# AVES_Telemetria_Eagle.net
KiCad netlist of a schematic drawn in EAGLE
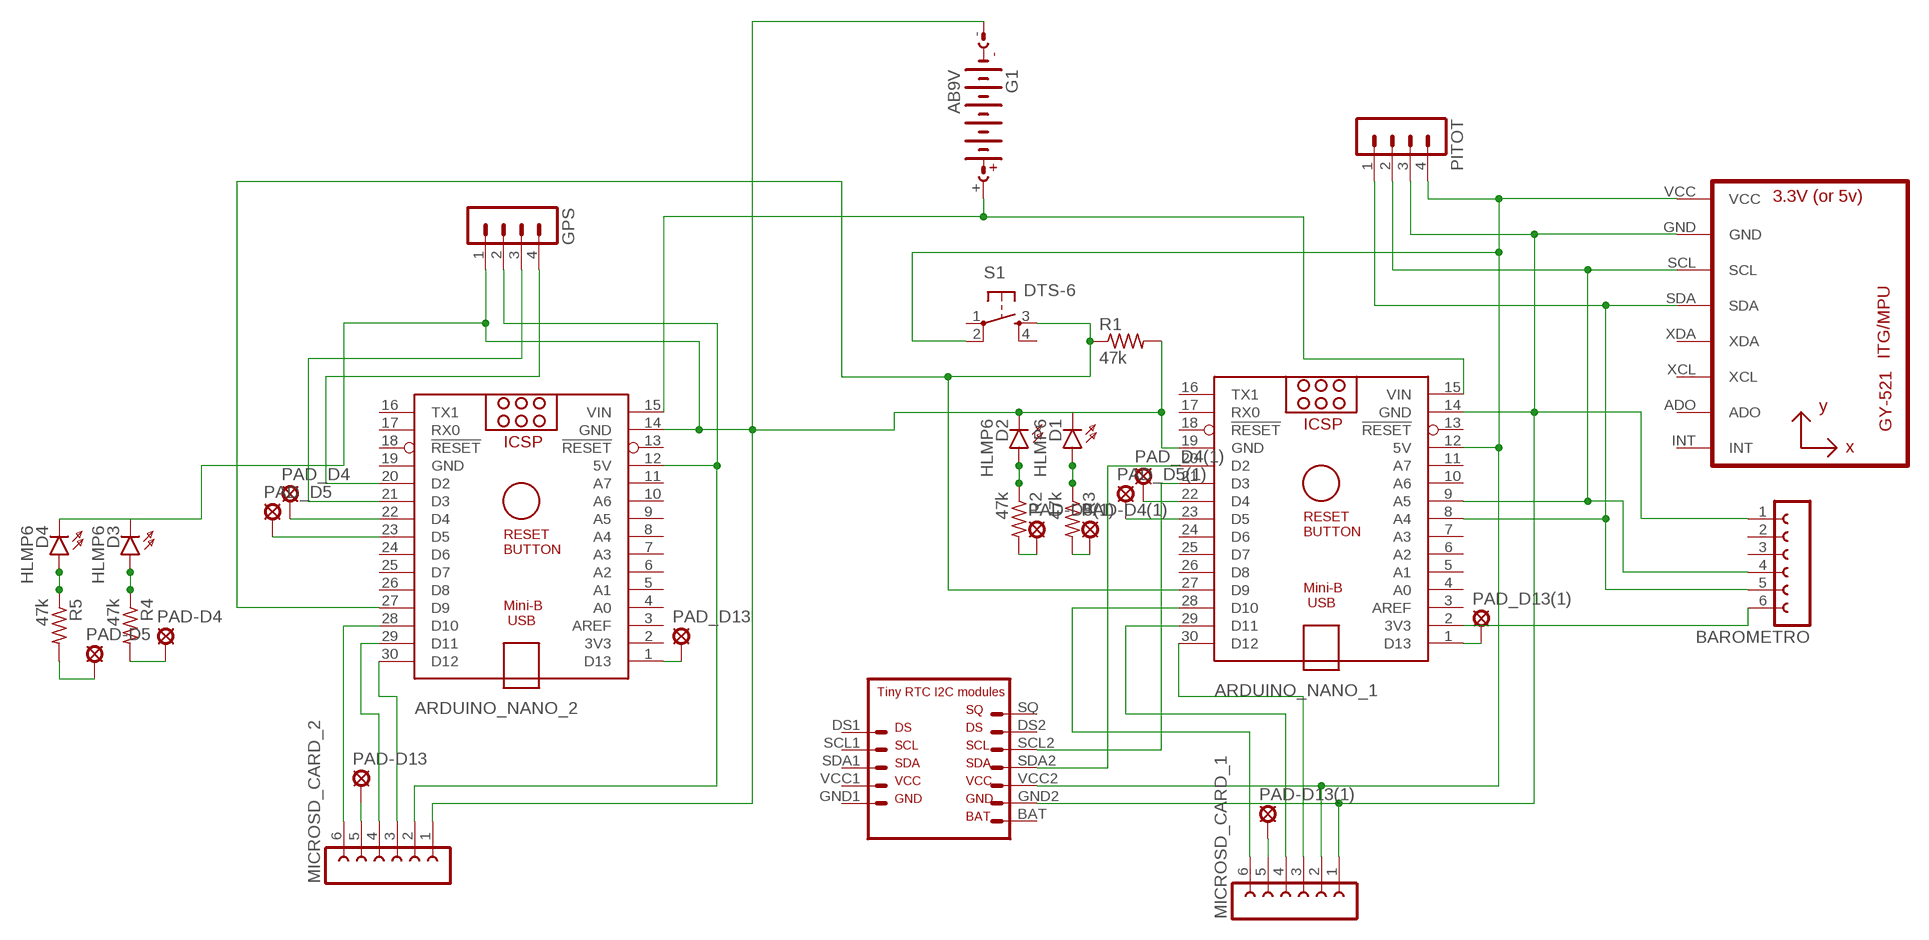
[diagram p0: schematic, sheet 1]

(export (version "E")
  (design (tool "Eeschema 10.0.6"))
  (components
    (comp (ref "ARDUINO_NANO_1")
      (value "ARDUINO_NANO")
      (footprint "eagle-import:ARDUINO_NANO")
      (libsource (lib "eagle-import") (part "ARDUINO_NANO"))
    )
    (comp (ref "ARDUINO_NANO_2")
      (value "ARDUINO_NANO")
      (footprint "eagle-import:ARDUINO_NANO")
      (libsource (lib "eagle-import") (part "ARDUINO_NANO"))
    )
    (comp (ref "BAROMETRO")
      (value "FE06-1")
      (footprint "eagle-import:FE06")
      (libsource (lib "eagle-import") (part "FE06-1"))
    )
    (comp (ref "D1")
      (value "HLMP6")
      (footprint "eagle-import:HLMP6")
      (fields (field (name "MF") "AGILENT TECHNOLOGIES") (field (name "MPN") "HLMP-6500"))
      (libsource (lib "eagle-import") (part "HLMP6"))
    )
    (comp (ref "D2")
      (value "HLMP6")
      (footprint "eagle-import:HLMP6")
      (fields (field (name "MF") "AGILENT TECHNOLOGIES") (field (name "MPN") "HLMP-6500"))
      (libsource (lib "eagle-import") (part "HLMP6"))
    )
    (comp (ref "D3")
      (value "HLMP6")
      (footprint "eagle-import:HLMP6")
      (fields (field (name "MF") "AGILENT TECHNOLOGIES") (field (name "MPN") "HLMP-6500"))
      (libsource (lib "eagle-import") (part "HLMP6"))
    )
    (comp (ref "D4")
      (value "HLMP6")
      (footprint "eagle-import:HLMP6")
      (fields (field (name "MF") "AGILENT TECHNOLOGIES") (field (name "MPN") "HLMP-6500"))
      (libsource (lib "eagle-import") (part "HLMP6"))
    )
    (comp (ref "G1")
      (value "AB9V")
      (footprint "eagle-import:AB9V")
      (libsource (lib "eagle-import") (part "AB9V"))
    )
    (comp (ref "GPS")
      (value "MA04-1")
      (footprint "eagle-import:MA04-1")
      (libsource (lib "eagle-import") (part "MA04-1"))
    )
    (comp (ref "MICROSD_CARD_1")
      (value "FE06-1")
      (footprint "eagle-import:FE06")
      (libsource (lib "eagle-import") (part "FE06-1"))
    )
    (comp (ref "MICROSD_CARD_2")
      (value "FE06-1")
      (footprint "eagle-import:FE06")
      (libsource (lib "eagle-import") (part "FE06-1"))
    )
    (comp (ref "PAD-D4")
      (value "LSP10")
      (footprint "eagle-import:LSP10")
      (libsource (lib "eagle-import") (part "LSP10"))
    )
    (comp (ref "PAD-D4(1)")
      (value "LSP10")
      (footprint "eagle-import:LSP10")
      (libsource (lib "eagle-import") (part "LSP10"))
    )
    (comp (ref "PAD-D5")
      (value "LSP10")
      (footprint "eagle-import:LSP10")
      (libsource (lib "eagle-import") (part "LSP10"))
    )
    (comp (ref "PAD-D5(1)")
      (value "LSP10")
      (footprint "eagle-import:LSP10")
      (libsource (lib "eagle-import") (part "LSP10"))
    )
    (comp (ref "PAD-D13")
      (value "LSP10")
      (footprint "eagle-import:LSP10")
      (libsource (lib "eagle-import") (part "LSP10"))
    )
    (comp (ref "PAD-D13(1)")
      (value "LSP10")
      (footprint "eagle-import:LSP10")
      (libsource (lib "eagle-import") (part "LSP10"))
    )
    (comp (ref "PAD_D4")
      (value "LSP10")
      (footprint "eagle-import:LSP10")
      (libsource (lib "eagle-import") (part "LSP10"))
    )
    (comp (ref "PAD_D4(1)")
      (value "LSP10")
      (footprint "eagle-import:LSP10")
      (libsource (lib "eagle-import") (part "LSP10"))
    )
    (comp (ref "PAD_D5")
      (value "LSP10")
      (footprint "eagle-import:LSP10")
      (libsource (lib "eagle-import") (part "LSP10"))
    )
    (comp (ref "PAD_D5(1)")
      (value "LSP10")
      (footprint "eagle-import:LSP10")
      (libsource (lib "eagle-import") (part "LSP10"))
    )
    (comp (ref "PAD_D13")
      (value "LSP10")
      (footprint "eagle-import:LSP10")
      (libsource (lib "eagle-import") (part "LSP10"))
    )
    (comp (ref "PAD_D13(1)")
      (value "LSP10")
      (footprint "eagle-import:LSP10")
      (libsource (lib "eagle-import") (part "LSP10"))
    )
    (comp (ref "PITOT")
      (value "MA04-1")
      (footprint "eagle-import:MA04-1")
      (libsource (lib "eagle-import") (part "MA04-1"))
    )
    (comp (ref "R1")
      (value "47k")
      (footprint "eagle-import:0204_5")
      (libsource (lib "eagle-import") (part "R-US_0204/5"))
    )
    (comp (ref "R2")
      (value "47k")
      (footprint "eagle-import:0204_5")
      (libsource (lib "eagle-import") (part "R-US_0204/5"))
    )
    (comp (ref "R3")
      (value "47k")
      (footprint "eagle-import:0204_5")
      (libsource (lib "eagle-import") (part "R-US_0204/5"))
    )
    (comp (ref "R4")
      (value "47k")
      (footprint "eagle-import:0204_5")
      (libsource (lib "eagle-import") (part "R-US_0204/5"))
    )
    (comp (ref "R5")
      (value "47k")
      (footprint "eagle-import:0204_5")
      (libsource (lib "eagle-import") (part "R-US_0204/5"))
    )
    (comp (ref "S1")
      (value "DTS-6")
      (footprint "eagle-import:DTS-6")
      (libsource (lib "eagle-import") (part "DTS-6"))
    )
    (comp (ref "U$1")
      (value "RTC")
      (footprint "eagle-import:RTC")
      (libsource (lib "eagle-import") (part "RTC"))
    )
    (comp (ref "U1")
      (value "GY-521MPU6050")
      (footprint "eagle-import:GY-521")
      (libsource (lib "eagle-import") (part "GY-521MPU6050"))
    )
  )
  (nets
    (net (code "1") (name "/GND") (class "Default")
      (node (ref "ARDUINO_NANO_2") (pin "19") (pinfunction "GND_19") (pintype "power_in"))
    )
    (net (code "2") (name "Net-(ARDUINO_NANO_1-3V3)") (class "Default")
      (node (ref "ARDUINO_NANO_1") (pin "2") (pinfunction "3V3_2") (pintype "output"))
      (node (ref "BAROMETRO") (pin "6") (pinfunction "6_6") (pintype "passive"))
    )
    (net (code "3") (name "Net-(ARDUINO_NANO_1-5V)") (class "Default")
      (node (ref "ARDUINO_NANO_1") (pin "12") (pinfunction "5V_12") (pintype "power_in"))
      (node (ref "MICROSD_CARD_1") (pin "2") (pinfunction "2_2") (pintype "passive"))
      (node (ref "PITOT") (pin "4") (pinfunction "4_4") (pintype "passive"))
      (node (ref "S1") (pin "2") (pinfunction "2_2") (pintype "passive"))
      (node (ref "U$1") (pin "VCC2") (pinfunction "VCC2_VCC2") (pintype "passive"))
      (node (ref "U1") (pin "VCC") (pinfunction "VCC_VCC") (pintype "bidirectional"))
    )
    (net (code "4") (name "Net-(ARDUINO_NANO_1-A4)") (class "Default")
      (node (ref "ARDUINO_NANO_1") (pin "8") (pinfunction "A4_8") (pintype "bidirectional"))
      (node (ref "BAROMETRO") (pin "5") (pinfunction "5_5") (pintype "passive"))
      (node (ref "PITOT") (pin "1") (pinfunction "1_1") (pintype "passive"))
      (node (ref "U1") (pin "SDA") (pinfunction "SDA_SDA") (pintype "bidirectional"))
    )
    (net (code "5") (name "Net-(ARDUINO_NANO_1-A5)") (class "Default")
      (node (ref "ARDUINO_NANO_1") (pin "9") (pinfunction "A5_9") (pintype "bidirectional"))
      (node (ref "BAROMETRO") (pin "4") (pinfunction "4_4") (pintype "passive"))
      (node (ref "PITOT") (pin "2") (pinfunction "2_2") (pintype "passive"))
      (node (ref "U1") (pin "SCL") (pinfunction "SCL_SCL") (pintype "bidirectional"))
    )
    (net (code "6") (name "Net-(ARDUINO_NANO_1-D2)") (class "Default")
      (node (ref "ARDUINO_NANO_1") (pin "20") (pinfunction "D2_20") (pintype "bidirectional"))
      (node (ref "U$1") (pin "SDA2") (pinfunction "SDA2_SDA2") (pintype "passive"))
    )
    (net (code "7") (name "Net-(ARDUINO_NANO_1-D3)") (class "Default")
      (node (ref "ARDUINO_NANO_1") (pin "21") (pinfunction "D3_21") (pintype "bidirectional"))
      (node (ref "U$1") (pin "SCL2") (pinfunction "SCL2_SCL2") (pintype "passive"))
    )
    (net (code "8") (name "Net-(ARDUINO_NANO_1-D4)") (class "Default")
      (node (ref "ARDUINO_NANO_1") (pin "22") (pinfunction "D4_22") (pintype "bidirectional"))
      (node (ref "PAD_D4(1)") (pin "MP") (pinfunction "MP_MP") (pintype "passive"))
    )
    (net (code "9") (name "Net-(ARDUINO_NANO_1-D5)") (class "Default")
      (node (ref "ARDUINO_NANO_1") (pin "23") (pinfunction "D5_23") (pintype "bidirectional"))
      (node (ref "PAD_D5(1)") (pin "MP") (pinfunction "MP_MP") (pintype "passive"))
    )
    (net (code "10") (name "Net-(ARDUINO_NANO_1-D9)") (class "Default")
      (node (ref "ARDUINO_NANO_1") (pin "27") (pinfunction "D9_27") (pintype "bidirectional"))
      (node (ref "ARDUINO_NANO_2") (pin "27") (pinfunction "D9_27") (pintype "bidirectional"))
      (node (ref "R1") (pin "1") (pinfunction "1_1") (pintype "passive"))
      (node (ref "S1") (pin "3") (pinfunction "3_3") (pintype "passive"))
    )
    (net (code "11") (name "Net-(ARDUINO_NANO_1-D10)") (class "Default")
      (node (ref "ARDUINO_NANO_1") (pin "28") (pinfunction "D10_28") (pintype "bidirectional"))
      (node (ref "MICROSD_CARD_1") (pin "6") (pinfunction "6_6") (pintype "passive"))
    )
    (net (code "12") (name "Net-(ARDUINO_NANO_1-D11)") (class "Default")
      (node (ref "ARDUINO_NANO_1") (pin "29") (pinfunction "D11_29") (pintype "bidirectional"))
      (node (ref "MICROSD_CARD_1") (pin "4") (pinfunction "4_4") (pintype "passive"))
    )
    (net (code "13") (name "Net-(ARDUINO_NANO_1-D12)") (class "Default")
      (node (ref "ARDUINO_NANO_1") (pin "30") (pinfunction "D12_30") (pintype "bidirectional"))
      (node (ref "MICROSD_CARD_1") (pin "3") (pinfunction "3_3") (pintype "passive"))
    )
    (net (code "14") (name "Net-(ARDUINO_NANO_1-D13)") (class "Default")
      (node (ref "ARDUINO_NANO_1") (pin "1") (pinfunction "D13_1") (pintype "bidirectional"))
      (node (ref "PAD_D13(1)") (pin "MP") (pinfunction "MP_MP") (pintype "passive"))
    )
    (net (code "15") (name "Net-(ARDUINO_NANO_1-GND-Pad14)") (class "Default")
      (node (ref "ARDUINO_NANO_1") (pin "14") (pinfunction "GND_14") (pintype "power_in"))
      (node (ref "BAROMETRO") (pin "1") (pinfunction "1_1") (pintype "passive"))
      (node (ref "MICROSD_CARD_1") (pin "1") (pinfunction "1_1") (pintype "passive"))
      (node (ref "PITOT") (pin "3") (pinfunction "3_3") (pintype "passive"))
      (node (ref "U$1") (pin "GND2") (pinfunction "GND2_GND2") (pintype "passive"))
      (node (ref "U1") (pin "GND") (pinfunction "GND_GND") (pintype "bidirectional"))
    )
    (net (code "16") (name "Net-(ARDUINO_NANO_1-GND-Pad19)") (class "Default")
      (node (ref "ARDUINO_NANO_1") (pin "19") (pinfunction "GND_19") (pintype "power_in"))
      (node (ref "ARDUINO_NANO_2") (pin "14") (pinfunction "GND_14") (pintype "power_in"))
      (node (ref "D1") (pin "K") (pinfunction "K_K") (pintype "passive"))
      (node (ref "D2") (pin "K") (pinfunction "K_K") (pintype "passive"))
      (node (ref "D3") (pin "K") (pinfunction "K_K") (pintype "passive"))
      (node (ref "D4") (pin "K") (pinfunction "K_K") (pintype "passive"))
      (node (ref "G1") (pin "-") (pinfunction "-_-") (pintype "passive"))
      (node (ref "GPS") (pin "1") (pinfunction "1_1") (pintype "passive"))
      (node (ref "MICROSD_CARD_2") (pin "1") (pinfunction "1_1") (pintype "passive"))
      (node (ref "R1") (pin "2") (pinfunction "2_2") (pintype "passive"))
    )
    (net (code "17") (name "Net-(ARDUINO_NANO_1-VIN)") (class "Default")
      (node (ref "ARDUINO_NANO_1") (pin "15") (pinfunction "VIN_15") (pintype "power_in"))
      (node (ref "ARDUINO_NANO_2") (pin "15") (pinfunction "VIN_15") (pintype "power_in"))
      (node (ref "G1") (pin "+") (pinfunction "+_+") (pintype "passive"))
    )
    (net (code "18") (name "Net-(ARDUINO_NANO_2-5V)") (class "Default")
      (node (ref "ARDUINO_NANO_2") (pin "12") (pinfunction "5V_12") (pintype "power_in"))
      (node (ref "GPS") (pin "2") (pinfunction "2_2") (pintype "passive"))
      (node (ref "MICROSD_CARD_2") (pin "2") (pinfunction "2_2") (pintype "passive"))
    )
    (net (code "19") (name "Net-(ARDUINO_NANO_2-D2)") (class "Default")
      (node (ref "ARDUINO_NANO_2") (pin "20") (pinfunction "D2_20") (pintype "bidirectional"))
      (node (ref "GPS") (pin "4") (pinfunction "4_4") (pintype "passive"))
    )
    (net (code "20") (name "Net-(ARDUINO_NANO_2-D3)") (class "Default")
      (node (ref "ARDUINO_NANO_2") (pin "21") (pinfunction "D3_21") (pintype "bidirectional"))
      (node (ref "GPS") (pin "3") (pinfunction "3_3") (pintype "passive"))
    )
    (net (code "21") (name "Net-(ARDUINO_NANO_2-D4)") (class "Default")
      (node (ref "ARDUINO_NANO_2") (pin "22") (pinfunction "D4_22") (pintype "bidirectional"))
      (node (ref "PAD_D4") (pin "MP") (pinfunction "MP_MP") (pintype "passive"))
    )
    (net (code "22") (name "Net-(ARDUINO_NANO_2-D5)") (class "Default")
      (node (ref "ARDUINO_NANO_2") (pin "23") (pinfunction "D5_23") (pintype "bidirectional"))
      (node (ref "PAD_D5") (pin "MP") (pinfunction "MP_MP") (pintype "passive"))
    )
    (net (code "23") (name "Net-(ARDUINO_NANO_2-D10)") (class "Default")
      (node (ref "ARDUINO_NANO_2") (pin "28") (pinfunction "D10_28") (pintype "bidirectional"))
      (node (ref "MICROSD_CARD_2") (pin "6") (pinfunction "6_6") (pintype "passive"))
    )
    (net (code "24") (name "Net-(ARDUINO_NANO_2-D11)") (class "Default")
      (node (ref "ARDUINO_NANO_2") (pin "29") (pinfunction "D11_29") (pintype "bidirectional"))
      (node (ref "MICROSD_CARD_2") (pin "4") (pinfunction "4_4") (pintype "passive"))
    )
    (net (code "25") (name "Net-(ARDUINO_NANO_2-D12)") (class "Default")
      (node (ref "ARDUINO_NANO_2") (pin "30") (pinfunction "D12_30") (pintype "bidirectional"))
      (node (ref "MICROSD_CARD_2") (pin "3") (pinfunction "3_3") (pintype "passive"))
    )
    (net (code "26") (name "Net-(ARDUINO_NANO_2-D13)") (class "Default")
      (node (ref "ARDUINO_NANO_2") (pin "1") (pinfunction "D13_1") (pintype "bidirectional"))
      (node (ref "PAD_D13") (pin "MP") (pinfunction "MP_MP") (pintype "passive"))
    )
    (net (code "27") (name "Net-(D1-PadA)") (class "Default")
      (node (ref "D1") (pin "A") (pinfunction "A_A") (pintype "passive"))
      (node (ref "R3") (pin "1") (pinfunction "1_1") (pintype "passive"))
    )
    (net (code "28") (name "Net-(D2-PadA)") (class "Default")
      (node (ref "D2") (pin "A") (pinfunction "A_A") (pintype "passive"))
      (node (ref "R2") (pin "1") (pinfunction "1_1") (pintype "passive"))
    )
    (net (code "29") (name "Net-(D3-PadA)") (class "Default")
      (node (ref "D3") (pin "A") (pinfunction "A_A") (pintype "passive"))
      (node (ref "R4") (pin "1") (pinfunction "1_1") (pintype "passive"))
    )
    (net (code "30") (name "Net-(D4-PadA)") (class "Default")
      (node (ref "D4") (pin "A") (pinfunction "A_A") (pintype "passive"))
      (node (ref "R5") (pin "1") (pinfunction "1_1") (pintype "passive"))
    )
    (net (code "31") (name "Net-(MICROSD_CARD_1-Pad5)") (class "Default")
      (node (ref "MICROSD_CARD_1") (pin "5") (pinfunction "5_5") (pintype "passive"))
      (node (ref "PAD-D13(1)") (pin "MP") (pinfunction "MP_MP") (pintype "passive"))
    )
    (net (code "32") (name "Net-(MICROSD_CARD_2-Pad5)") (class "Default")
      (node (ref "MICROSD_CARD_2") (pin "5") (pinfunction "5_5") (pintype "passive"))
      (node (ref "PAD-D13") (pin "MP") (pinfunction "MP_MP") (pintype "passive"))
    )
    (net (code "33") (name "Net-(PAD-D4(1)-PadMP)") (class "Default")
      (node (ref "PAD-D4(1)") (pin "MP") (pinfunction "MP_MP") (pintype "passive"))
      (node (ref "R3") (pin "2") (pinfunction "2_2") (pintype "passive"))
    )
    (net (code "34") (name "Net-(PAD-D4-PadMP)") (class "Default")
      (node (ref "PAD-D4") (pin "MP") (pinfunction "MP_MP") (pintype "passive"))
      (node (ref "R4") (pin "2") (pinfunction "2_2") (pintype "passive"))
    )
    (net (code "35") (name "Net-(PAD-D5(1)-PadMP)") (class "Default")
      (node (ref "PAD-D5(1)") (pin "MP") (pinfunction "MP_MP") (pintype "passive"))
      (node (ref "R2") (pin "2") (pinfunction "2_2") (pintype "passive"))
    )
    (net (code "36") (name "Net-(PAD-D5-PadMP)") (class "Default")
      (node (ref "PAD-D5") (pin "MP") (pinfunction "MP_MP") (pintype "passive"))
      (node (ref "R5") (pin "2") (pinfunction "2_2") (pintype "passive"))
    )
    (net (code "37") (name "unconnected-(ARDUINO_NANO_1-A0-Pad4)") (class "Default")
      (node (ref "ARDUINO_NANO_1") (pin "4") (pinfunction "A0_4") (pintype "bidirectional"))
    )
    (net (code "38") (name "unconnected-(ARDUINO_NANO_1-A1-Pad5)") (class "Default")
      (node (ref "ARDUINO_NANO_1") (pin "5") (pinfunction "A1_5") (pintype "bidirectional"))
    )
    (net (code "39") (name "unconnected-(ARDUINO_NANO_1-A2-Pad6)") (class "Default")
      (node (ref "ARDUINO_NANO_1") (pin "6") (pinfunction "A2_6") (pintype "bidirectional"))
    )
    (net (code "40") (name "unconnected-(ARDUINO_NANO_1-A3-Pad7)") (class "Default")
      (node (ref "ARDUINO_NANO_1") (pin "7") (pinfunction "A3_7") (pintype "bidirectional"))
    )
    (net (code "41") (name "unconnected-(ARDUINO_NANO_1-A6-Pad10)") (class "Default")
      (node (ref "ARDUINO_NANO_1") (pin "10") (pinfunction "A6_10") (pintype "bidirectional"))
    )
    (net (code "42") (name "unconnected-(ARDUINO_NANO_1-A7-Pad11)") (class "Default")
      (node (ref "ARDUINO_NANO_1") (pin "11") (pinfunction "A7_11") (pintype "bidirectional"))
    )
    (net (code "43") (name "unconnected-(ARDUINO_NANO_1-AREF-Pad3)") (class "Default")
      (node (ref "ARDUINO_NANO_1") (pin "3") (pinfunction "AREF_3") (pintype "input"))
    )
    (net (code "44") (name "unconnected-(ARDUINO_NANO_1-D6-Pad24)") (class "Default")
      (node (ref "ARDUINO_NANO_1") (pin "24") (pinfunction "D6_24") (pintype "bidirectional"))
    )
    (net (code "45") (name "unconnected-(ARDUINO_NANO_1-D7-Pad25)") (class "Default")
      (node (ref "ARDUINO_NANO_1") (pin "25") (pinfunction "D7_25") (pintype "bidirectional"))
    )
    (net (code "46") (name "unconnected-(ARDUINO_NANO_1-D8-Pad26)") (class "Default")
      (node (ref "ARDUINO_NANO_1") (pin "26") (pinfunction "D8_26") (pintype "bidirectional"))
    )
    (net (code "47") (name "unconnected-(ARDUINO_NANO_1-RX0-Pad17)") (class "Default")
      (node (ref "ARDUINO_NANO_1") (pin "17") (pinfunction "RX0_17") (pintype "bidirectional"))
    )
    (net (code "48") (name "unconnected-(ARDUINO_NANO_1-TX1-Pad16)") (class "Default")
      (node (ref "ARDUINO_NANO_1") (pin "16") (pinfunction "TX1_16") (pintype "bidirectional"))
    )
    (net (code "49") (name "unconnected-(ARDUINO_NANO_1-~{RESET}-Pad13)") (class "Default")
      (node (ref "ARDUINO_NANO_1") (pin "13") (pinfunction "~{RESET}_13") (pintype "input"))
    )
    (net (code "50") (name "unconnected-(ARDUINO_NANO_1-~{RESET}-Pad18)") (class "Default")
      (node (ref "ARDUINO_NANO_1") (pin "18") (pinfunction "~{RESET}_18") (pintype "input"))
    )
    (net (code "51") (name "unconnected-(ARDUINO_NANO_2-3V3-Pad2)") (class "Default")
      (node (ref "ARDUINO_NANO_2") (pin "2") (pinfunction "3V3_2") (pintype "output"))
    )
    (net (code "52") (name "unconnected-(ARDUINO_NANO_2-A0-Pad4)") (class "Default")
      (node (ref "ARDUINO_NANO_2") (pin "4") (pinfunction "A0_4") (pintype "bidirectional"))
    )
    (net (code "53") (name "unconnected-(ARDUINO_NANO_2-A1-Pad5)") (class "Default")
      (node (ref "ARDUINO_NANO_2") (pin "5") (pinfunction "A1_5") (pintype "bidirectional"))
    )
    (net (code "54") (name "unconnected-(ARDUINO_NANO_2-A2-Pad6)") (class "Default")
      (node (ref "ARDUINO_NANO_2") (pin "6") (pinfunction "A2_6") (pintype "bidirectional"))
    )
    (net (code "55") (name "unconnected-(ARDUINO_NANO_2-A3-Pad7)") (class "Default")
      (node (ref "ARDUINO_NANO_2") (pin "7") (pinfunction "A3_7") (pintype "bidirectional"))
    )
    (net (code "56") (name "unconnected-(ARDUINO_NANO_2-A4-Pad8)") (class "Default")
      (node (ref "ARDUINO_NANO_2") (pin "8") (pinfunction "A4_8") (pintype "bidirectional"))
    )
    (net (code "57") (name "unconnected-(ARDUINO_NANO_2-A5-Pad9)") (class "Default")
      (node (ref "ARDUINO_NANO_2") (pin "9") (pinfunction "A5_9") (pintype "bidirectional"))
    )
    (net (code "58") (name "unconnected-(ARDUINO_NANO_2-A6-Pad10)") (class "Default")
      (node (ref "ARDUINO_NANO_2") (pin "10") (pinfunction "A6_10") (pintype "bidirectional"))
    )
    (net (code "59") (name "unconnected-(ARDUINO_NANO_2-A7-Pad11)") (class "Default")
      (node (ref "ARDUINO_NANO_2") (pin "11") (pinfunction "A7_11") (pintype "bidirectional"))
    )
    (net (code "60") (name "unconnected-(ARDUINO_NANO_2-AREF-Pad3)") (class "Default")
      (node (ref "ARDUINO_NANO_2") (pin "3") (pinfunction "AREF_3") (pintype "input"))
    )
    (net (code "61") (name "unconnected-(ARDUINO_NANO_2-D6-Pad24)") (class "Default")
      (node (ref "ARDUINO_NANO_2") (pin "24") (pinfunction "D6_24") (pintype "bidirectional"))
    )
    (net (code "62") (name "unconnected-(ARDUINO_NANO_2-D7-Pad25)") (class "Default")
      (node (ref "ARDUINO_NANO_2") (pin "25") (pinfunction "D7_25") (pintype "bidirectional"))
    )
    (net (code "63") (name "unconnected-(ARDUINO_NANO_2-D8-Pad26)") (class "Default")
      (node (ref "ARDUINO_NANO_2") (pin "26") (pinfunction "D8_26") (pintype "bidirectional"))
    )
    (net (code "64") (name "unconnected-(ARDUINO_NANO_2-RX0-Pad17)") (class "Default")
      (node (ref "ARDUINO_NANO_2") (pin "17") (pinfunction "RX0_17") (pintype "bidirectional"))
    )
    (net (code "65") (name "unconnected-(ARDUINO_NANO_2-TX1-Pad16)") (class "Default")
      (node (ref "ARDUINO_NANO_2") (pin "16") (pinfunction "TX1_16") (pintype "bidirectional"))
    )
    (net (code "66") (name "unconnected-(ARDUINO_NANO_2-~{RESET}-Pad13)") (class "Default")
      (node (ref "ARDUINO_NANO_2") (pin "13") (pinfunction "~{RESET}_13") (pintype "input"))
    )
    (net (code "67") (name "unconnected-(ARDUINO_NANO_2-~{RESET}-Pad18)") (class "Default")
      (node (ref "ARDUINO_NANO_2") (pin "18") (pinfunction "~{RESET}_18") (pintype "input"))
    )
    (net (code "68") (name "unconnected-(BAROMETRO-Pad2)") (class "Default")
      (node (ref "BAROMETRO") (pin "2") (pinfunction "2_2") (pintype "passive"))
    )
    (net (code "69") (name "unconnected-(BAROMETRO-Pad3)") (class "Default")
      (node (ref "BAROMETRO") (pin "3") (pinfunction "3_3") (pintype "passive"))
    )
    (net (code "70") (name "unconnected-(S1-Pad1)") (class "Default")
      (node (ref "S1") (pin "1") (pinfunction "1_1") (pintype "passive"))
    )
    (net (code "71") (name "unconnected-(S1-Pad4)") (class "Default")
      (node (ref "S1") (pin "4") (pinfunction "4_4") (pintype "passive"))
    )
    (net (code "72") (name "unconnected-(U$1-PadBAT)") (class "Default")
      (node (ref "U$1") (pin "BAT") (pinfunction "BAT_BAT") (pintype "passive"))
    )
    (net (code "73") (name "unconnected-(U$1-PadDS1)") (class "Default")
      (node (ref "U$1") (pin "DS1") (pinfunction "DS1_DS1") (pintype "passive"))
    )
    (net (code "74") (name "unconnected-(U$1-PadDS2)") (class "Default")
      (node (ref "U$1") (pin "DS2") (pinfunction "DS2_DS2") (pintype "passive"))
    )
    (net (code "75") (name "unconnected-(U$1-PadGND1)") (class "Default")
      (node (ref "U$1") (pin "GND1") (pinfunction "GND1_GND1") (pintype "passive"))
    )
    (net (code "76") (name "unconnected-(U$1-PadSCL1)") (class "Default")
      (node (ref "U$1") (pin "SCL1") (pinfunction "SCL1_SCL1") (pintype "passive"))
    )
    (net (code "77") (name "unconnected-(U$1-PadSDA1)") (class "Default")
      (node (ref "U$1") (pin "SDA1") (pinfunction "SDA1_SDA1") (pintype "passive"))
    )
    (net (code "78") (name "unconnected-(U$1-PadSQ)") (class "Default")
      (node (ref "U$1") (pin "SQ") (pinfunction "SQ_SQ") (pintype "passive"))
    )
    (net (code "79") (name "unconnected-(U$1-PadVCC1)") (class "Default")
      (node (ref "U$1") (pin "VCC1") (pinfunction "VCC1_VCC1") (pintype "passive"))
    )
    (net (code "80") (name "unconnected-(U1-PadADO)") (class "Default")
      (node (ref "U1") (pin "ADO") (pinfunction "ADO_ADO") (pintype "bidirectional"))
    )
    (net (code "81") (name "unconnected-(U1-PadINT)") (class "Default")
      (node (ref "U1") (pin "INT") (pinfunction "INT_INT") (pintype "bidirectional"))
    )
    (net (code "82") (name "unconnected-(U1-PadXCL)") (class "Default")
      (node (ref "U1") (pin "XCL") (pinfunction "XCL_XCL") (pintype "bidirectional"))
    )
    (net (code "83") (name "unconnected-(U1-PadXDA)") (class "Default")
      (node (ref "U1") (pin "XDA") (pinfunction "XDA_XDA") (pintype "bidirectional"))
    )
  )
)
